# ab_v10.net
KiCad netlist of a schematic drawn in EAGLE
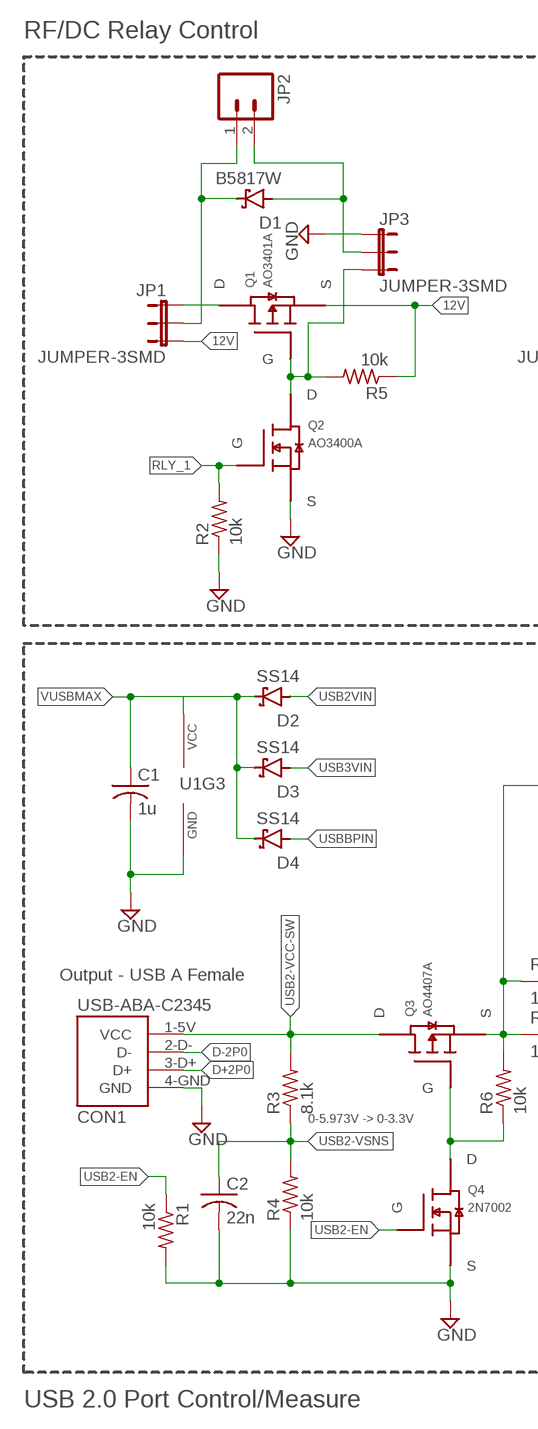
[diagram p0: schematic, sheet 1, part 1 of 2]
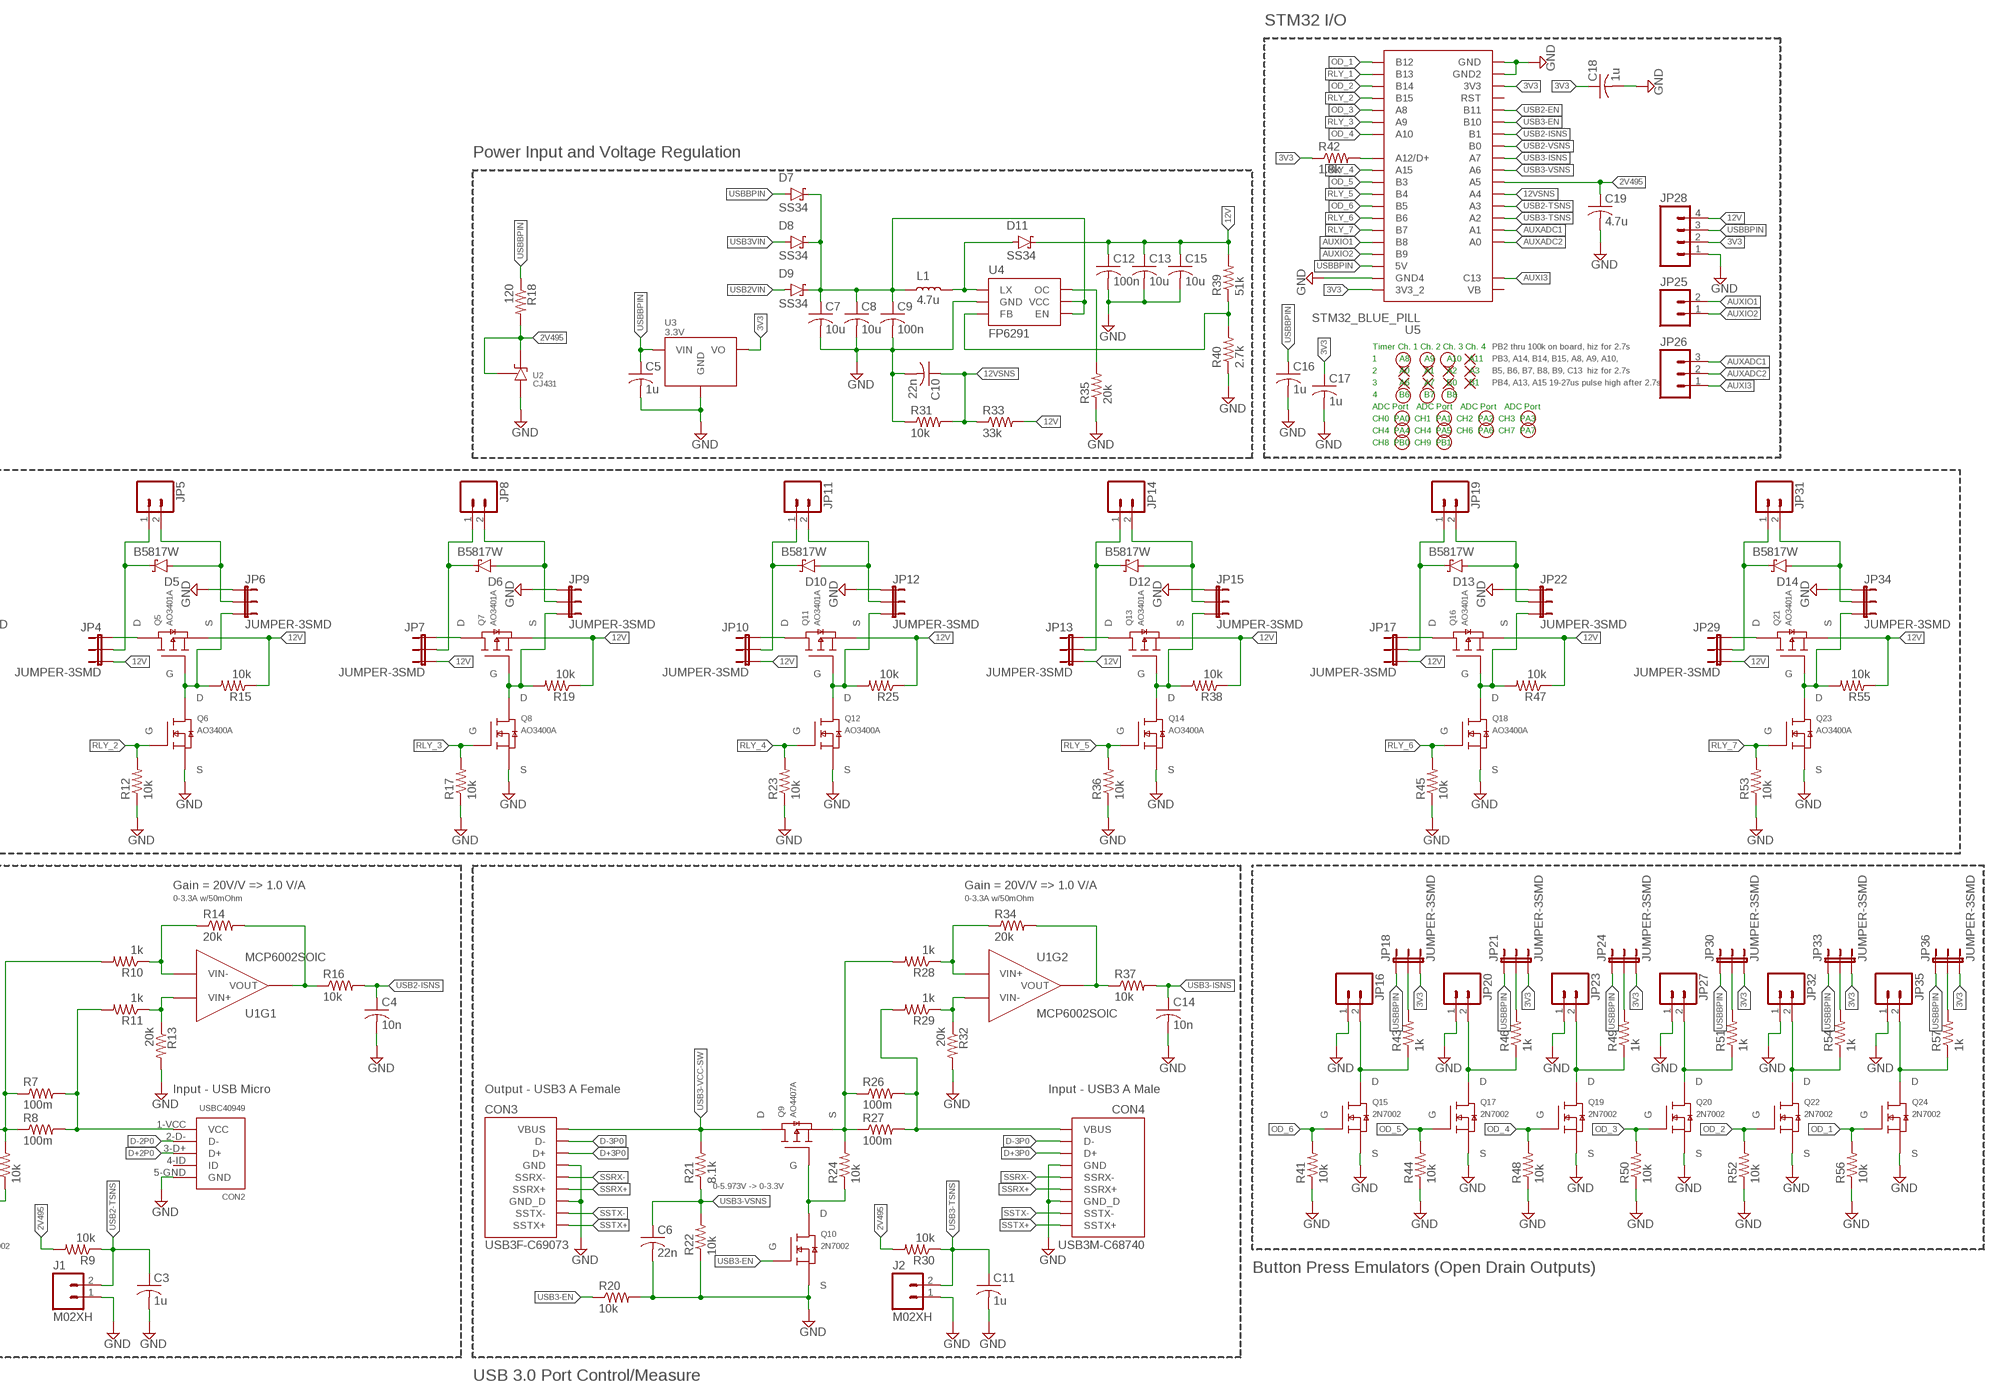
[diagram p1: schematic, sheet 1, part 2 of 2]

(export (version "E")
  (design (tool "Eeschema 10.0.6"))
  (components
    (comp (ref "C1")
      (value "1u")
      (footprint "eagle-import:C0402")
      (libsource (lib "eagle-import") (part "C-USC0402"))
    )
    (comp (ref "C2")
      (value "22n")
      (footprint "eagle-import:C0402")
      (libsource (lib "eagle-import") (part "C-USC0402"))
    )
    (comp (ref "C3")
      (value "1u")
      (footprint "eagle-import:C0402")
      (libsource (lib "eagle-import") (part "C-USC0402"))
    )
    (comp (ref "C4")
      (value "10n")
      (footprint "eagle-import:C0402")
      (libsource (lib "eagle-import") (part "C-USC0402"))
    )
    (comp (ref "C5")
      (value "1u")
      (footprint "eagle-import:C0402")
      (libsource (lib "eagle-import") (part "C-USC0402"))
    )
    (comp (ref "C6")
      (value "22n")
      (footprint "eagle-import:C0402")
      (libsource (lib "eagle-import") (part "C-USC0402"))
    )
    (comp (ref "C7")
      (value "10u")
      (footprint "eagle-import:C0603")
      (libsource (lib "eagle-import") (part "C-USC0603"))
    )
    (comp (ref "C8")
      (value "10u")
      (footprint "eagle-import:C0603")
      (libsource (lib "eagle-import") (part "C-USC0603"))
    )
    (comp (ref "C9")
      (value "100n")
      (footprint "eagle-import:C0402")
      (libsource (lib "eagle-import") (part "C-USC0402"))
    )
    (comp (ref "C10")
      (value "22n")
      (footprint "eagle-import:C0402")
      (libsource (lib "eagle-import") (part "C-USC0402"))
    )
    (comp (ref "C11")
      (value "1u")
      (footprint "eagle-import:C0402")
      (libsource (lib "eagle-import") (part "C-USC0402"))
    )
    (comp (ref "C12")
      (value "100n")
      (footprint "eagle-import:C0402")
      (libsource (lib "eagle-import") (part "C-USC0402"))
    )
    (comp (ref "C13")
      (value "10u")
      (footprint "eagle-import:C0805")
      (libsource (lib "eagle-import") (part "C-USC0805"))
    )
    (comp (ref "C14")
      (value "10n")
      (footprint "eagle-import:C0402")
      (libsource (lib "eagle-import") (part "C-USC0402"))
    )
    (comp (ref "C15")
      (value "10u")
      (footprint "eagle-import:C0805")
      (libsource (lib "eagle-import") (part "C-USC0805"))
    )
    (comp (ref "C16")
      (value "1u")
      (footprint "eagle-import:C0402")
      (libsource (lib "eagle-import") (part "C-USC0402"))
    )
    (comp (ref "C17")
      (value "1u")
      (footprint "eagle-import:C0402")
      (libsource (lib "eagle-import") (part "C-USC0402"))
    )
    (comp (ref "C18")
      (value "1u")
      (footprint "eagle-import:C0402")
      (libsource (lib "eagle-import") (part "C-USC0402"))
    )
    (comp (ref "C19")
      (value "4.7u")
      (footprint "eagle-import:C0402")
      (libsource (lib "eagle-import") (part "C-USC0402"))
    )
    (comp (ref "CON1")
      (value "USB-ABA-C2345")
      (footprint "eagle-import:USB_A_C2345")
      (libsource (lib "eagle-import") (part "USB-ABA-C2345"))
    )
    (comp (ref "CON2")
      (value "USBC40949")
      (footprint "eagle-import:MICRO_USB-B_C40949")
      (libsource (lib "eagle-import") (part "USBC40949"))
    )
    (comp (ref "CON3")
      (value "USB3F-C69073")
      (footprint "eagle-import:USB3-F-C69073")
      (libsource (lib "eagle-import") (part "USB3F-C69073"))
    )
    (comp (ref "CON4")
      (value "USB3M-C68740")
      (footprint "eagle-import:USB3-M-C68740")
      (libsource (lib "eagle-import") (part "USB3M-C68740"))
    )
    (comp (ref "D1")
      (value "B5817W")
      (footprint "eagle-import:SOD123W")
      (libsource (lib "eagle-import") (part "PMEG3020ER"))
    )
    (comp (ref "D2")
      (value "SS14")
      (footprint "eagle-import:SMA")
      (libsource (lib "eagle-import") (part "DIODE_SCHOTTKY_SMSSMA"))
    )
    (comp (ref "D3")
      (value "SS14")
      (footprint "eagle-import:SMA")
      (libsource (lib "eagle-import") (part "DIODE_SCHOTTKY_SMSSMA"))
    )
    (comp (ref "D4")
      (value "SS14")
      (footprint "eagle-import:SMA")
      (libsource (lib "eagle-import") (part "DIODE_SCHOTTKY_SMSSMA"))
    )
    (comp (ref "D5")
      (value "B5817W")
      (footprint "eagle-import:SOD123W")
      (libsource (lib "eagle-import") (part "PMEG3020ER"))
    )
    (comp (ref "D6")
      (value "B5817W")
      (footprint "eagle-import:SOD123W")
      (libsource (lib "eagle-import") (part "PMEG3020ER"))
    )
    (comp (ref "D7")
      (value "SS34")
      (footprint "eagle-import:SMA")
      (libsource (lib "eagle-import") (part "DIODE_SCHOTTKY_SMSSMA"))
    )
    (comp (ref "D8")
      (value "SS34")
      (footprint "eagle-import:SMA")
      (libsource (lib "eagle-import") (part "DIODE_SCHOTTKY_SMSSMA"))
    )
    (comp (ref "D9")
      (value "SS34")
      (footprint "eagle-import:SMA")
      (libsource (lib "eagle-import") (part "DIODE_SCHOTTKY_SMSSMA"))
    )
    (comp (ref "D10")
      (value "B5817W")
      (footprint "eagle-import:SOD123W")
      (libsource (lib "eagle-import") (part "PMEG3020ER"))
    )
    (comp (ref "D11")
      (value "SS34")
      (footprint "eagle-import:SMA")
      (libsource (lib "eagle-import") (part "DIODE_SCHOTTKY_SMSSMA"))
    )
    (comp (ref "D12")
      (value "B5817W")
      (footprint "eagle-import:SOD123W")
      (libsource (lib "eagle-import") (part "PMEG3020ER"))
    )
    (comp (ref "D13")
      (value "B5817W")
      (footprint "eagle-import:SOD123W")
      (libsource (lib "eagle-import") (part "PMEG3020ER"))
    )
    (comp (ref "D14")
      (value "B5817W")
      (footprint "eagle-import:SOD123W")
      (libsource (lib "eagle-import") (part "PMEG3020ER"))
    )
    (comp (ref "J1")
      (value "M02XH")
      (footprint "eagle-import:B2B-XH-A")
      (libsource (lib "eagle-import") (part "M02XH"))
    )
    (comp (ref "J2")
      (value "M02XH")
      (footprint "eagle-import:B2B-XH-A")
      (libsource (lib "eagle-import") (part "M02XH"))
    )
    (comp (ref "JP1")
      (value "JUMPER-3SMD")
      (footprint "eagle-import:SJ_3")
      (libsource (lib "eagle-import") (part "JUMPER-3SMD"))
    )
    (comp (ref "JP2")
      (value "M02PTH")
      (footprint "eagle-import:1X02")
      (libsource (lib "eagle-import") (part "M02PTH"))
    )
    (comp (ref "JP3")
      (value "JUMPER-3SMD")
      (footprint "eagle-import:SJ_3")
      (libsource (lib "eagle-import") (part "JUMPER-3SMD"))
    )
    (comp (ref "JP4")
      (value "JUMPER-3SMD")
      (footprint "eagle-import:SJ_3")
      (libsource (lib "eagle-import") (part "JUMPER-3SMD"))
    )
    (comp (ref "JP5")
      (value "M02PTH")
      (footprint "eagle-import:1X02")
      (libsource (lib "eagle-import") (part "M02PTH"))
    )
    (comp (ref "JP6")
      (value "JUMPER-3SMD")
      (footprint "eagle-import:SJ_3")
      (libsource (lib "eagle-import") (part "JUMPER-3SMD"))
    )
    (comp (ref "JP7")
      (value "JUMPER-3SMD")
      (footprint "eagle-import:SJ_3")
      (libsource (lib "eagle-import") (part "JUMPER-3SMD"))
    )
    (comp (ref "JP8")
      (value "M02PTH")
      (footprint "eagle-import:1X02")
      (libsource (lib "eagle-import") (part "M02PTH"))
    )
    (comp (ref "JP9")
      (value "JUMPER-3SMD")
      (footprint "eagle-import:SJ_3")
      (libsource (lib "eagle-import") (part "JUMPER-3SMD"))
    )
    (comp (ref "JP10")
      (value "JUMPER-3SMD")
      (footprint "eagle-import:SJ_3")
      (libsource (lib "eagle-import") (part "JUMPER-3SMD"))
    )
    (comp (ref "JP11")
      (value "M02PTH")
      (footprint "eagle-import:1X02")
      (libsource (lib "eagle-import") (part "M02PTH"))
    )
    (comp (ref "JP12")
      (value "JUMPER-3SMD")
      (footprint "eagle-import:SJ_3")
      (libsource (lib "eagle-import") (part "JUMPER-3SMD"))
    )
    (comp (ref "JP13")
      (value "JUMPER-3SMD")
      (footprint "eagle-import:SJ_3")
      (libsource (lib "eagle-import") (part "JUMPER-3SMD"))
    )
    (comp (ref "JP14")
      (value "M02PTH")
      (footprint "eagle-import:1X02")
      (libsource (lib "eagle-import") (part "M02PTH"))
    )
    (comp (ref "JP15")
      (value "JUMPER-3SMD")
      (footprint "eagle-import:SJ_3")
      (libsource (lib "eagle-import") (part "JUMPER-3SMD"))
    )
    (comp (ref "JP16")
      (value "M02PTH")
      (footprint "eagle-import:1X02")
      (libsource (lib "eagle-import") (part "M02PTH"))
    )
    (comp (ref "JP17")
      (value "JUMPER-3SMD")
      (footprint "eagle-import:SJ_3")
      (libsource (lib "eagle-import") (part "JUMPER-3SMD"))
    )
    (comp (ref "JP18")
      (value "JUMPER-3SMD")
      (footprint "eagle-import:SJ_3")
      (libsource (lib "eagle-import") (part "JUMPER-3SMD"))
    )
    (comp (ref "JP19")
      (value "M02PTH")
      (footprint "eagle-import:1X02")
      (libsource (lib "eagle-import") (part "M02PTH"))
    )
    (comp (ref "JP20")
      (value "M02PTH")
      (footprint "eagle-import:1X02")
      (libsource (lib "eagle-import") (part "M02PTH"))
    )
    (comp (ref "JP21")
      (value "JUMPER-3SMD")
      (footprint "eagle-import:SJ_3")
      (libsource (lib "eagle-import") (part "JUMPER-3SMD"))
    )
    (comp (ref "JP22")
      (value "JUMPER-3SMD")
      (footprint "eagle-import:SJ_3")
      (libsource (lib "eagle-import") (part "JUMPER-3SMD"))
    )
    (comp (ref "JP23")
      (value "M02PTH")
      (footprint "eagle-import:1X02")
      (libsource (lib "eagle-import") (part "M02PTH"))
    )
    (comp (ref "JP24")
      (value "JUMPER-3SMD")
      (footprint "eagle-import:SJ_3")
      (libsource (lib "eagle-import") (part "JUMPER-3SMD"))
    )
    (comp (ref "JP25")
      (value "M02PTH")
      (footprint "eagle-import:1X02")
      (libsource (lib "eagle-import") (part "M02PTH"))
    )
    (comp (ref "JP26")
      (value "M03PTH")
      (footprint "eagle-import:1X03")
      (libsource (lib "eagle-import") (part "M03PTH"))
    )
    (comp (ref "JP27")
      (value "M02PTH")
      (footprint "eagle-import:1X02")
      (libsource (lib "eagle-import") (part "M02PTH"))
    )
    (comp (ref "JP28")
      (value "M04PTH")
      (footprint "eagle-import:1X04")
      (libsource (lib "eagle-import") (part "M04PTH"))
    )
    (comp (ref "JP29")
      (value "JUMPER-3SMD")
      (footprint "eagle-import:SJ_3")
      (libsource (lib "eagle-import") (part "JUMPER-3SMD"))
    )
    (comp (ref "JP30")
      (value "JUMPER-3SMD")
      (footprint "eagle-import:SJ_3")
      (libsource (lib "eagle-import") (part "JUMPER-3SMD"))
    )
    (comp (ref "JP31")
      (value "M02PTH")
      (footprint "eagle-import:1X02")
      (libsource (lib "eagle-import") (part "M02PTH"))
    )
    (comp (ref "JP32")
      (value "M02PTH")
      (footprint "eagle-import:1X02")
      (libsource (lib "eagle-import") (part "M02PTH"))
    )
    (comp (ref "JP33")
      (value "JUMPER-3SMD")
      (footprint "eagle-import:SJ_3")
      (libsource (lib "eagle-import") (part "JUMPER-3SMD"))
    )
    (comp (ref "JP34")
      (value "JUMPER-3SMD")
      (footprint "eagle-import:SJ_3")
      (libsource (lib "eagle-import") (part "JUMPER-3SMD"))
    )
    (comp (ref "JP35")
      (value "M02PTH")
      (footprint "eagle-import:1X02")
      (libsource (lib "eagle-import") (part "M02PTH"))
    )
    (comp (ref "JP36")
      (value "JUMPER-3SMD")
      (footprint "eagle-import:SJ_3")
      (libsource (lib "eagle-import") (part "JUMPER-3SMD"))
    )
    (comp (ref "L1")
      (value "4.7u")
      (footprint "eagle-import:INDUCTOR_6X6")
      (libsource (lib "eagle-import") (part "INDUCTOR6X6"))
    )
    (comp (ref "Q1")
      (value "AO3401A")
      (footprint "eagle-import:SOT23")
      (libsource (lib "eagle-import") (part "AO3401A"))
    )
    (comp (ref "Q2")
      (value "AO3400A")
      (footprint "eagle-import:SOT23")
      (libsource (lib "eagle-import") (part "2N7002P"))
    )
    (comp (ref "Q3")
      (value "AO4407A")
      (footprint "eagle-import:8-SOIC")
      (libsource (lib "eagle-import") (part "P-MOSFET-SOIC8"))
    )
    (comp (ref "Q4")
      (value "2N7002")
      (footprint "eagle-import:SOT23")
      (libsource (lib "eagle-import") (part "2N7002P"))
    )
    (comp (ref "Q5")
      (value "AO3401A")
      (footprint "eagle-import:SOT23")
      (libsource (lib "eagle-import") (part "AO3401A"))
    )
    (comp (ref "Q6")
      (value "AO3400A")
      (footprint "eagle-import:SOT23")
      (libsource (lib "eagle-import") (part "2N7002P"))
    )
    (comp (ref "Q7")
      (value "AO3401A")
      (footprint "eagle-import:SOT23")
      (libsource (lib "eagle-import") (part "AO3401A"))
    )
    (comp (ref "Q8")
      (value "AO3400A")
      (footprint "eagle-import:SOT23")
      (libsource (lib "eagle-import") (part "2N7002P"))
    )
    (comp (ref "Q9")
      (value "AO4407A")
      (footprint "eagle-import:8-SOIC")
      (libsource (lib "eagle-import") (part "P-MOSFET-SOIC8"))
    )
    (comp (ref "Q10")
      (value "2N7002")
      (footprint "eagle-import:SOT23")
      (libsource (lib "eagle-import") (part "2N7002P"))
    )
    (comp (ref "Q11")
      (value "AO3401A")
      (footprint "eagle-import:SOT23")
      (libsource (lib "eagle-import") (part "AO3401A"))
    )
    (comp (ref "Q12")
      (value "AO3400A")
      (footprint "eagle-import:SOT23")
      (libsource (lib "eagle-import") (part "2N7002P"))
    )
    (comp (ref "Q13")
      (value "AO3401A")
      (footprint "eagle-import:SOT23")
      (libsource (lib "eagle-import") (part "AO3401A"))
    )
    (comp (ref "Q14")
      (value "AO3400A")
      (footprint "eagle-import:SOT23")
      (libsource (lib "eagle-import") (part "2N7002P"))
    )
    (comp (ref "Q15")
      (value "2N7002")
      (footprint "eagle-import:SOT23")
      (libsource (lib "eagle-import") (part "2N7002P"))
    )
    (comp (ref "Q16")
      (value "AO3401A")
      (footprint "eagle-import:SOT23")
      (libsource (lib "eagle-import") (part "AO3401A"))
    )
    (comp (ref "Q17")
      (value "2N7002")
      (footprint "eagle-import:SOT23")
      (libsource (lib "eagle-import") (part "2N7002P"))
    )
    (comp (ref "Q18")
      (value "AO3400A")
      (footprint "eagle-import:SOT23")
      (libsource (lib "eagle-import") (part "2N7002P"))
    )
    (comp (ref "Q19")
      (value "2N7002")
      (footprint "eagle-import:SOT23")
      (libsource (lib "eagle-import") (part "2N7002P"))
    )
    (comp (ref "Q20")
      (value "2N7002")
      (footprint "eagle-import:SOT23")
      (libsource (lib "eagle-import") (part "2N7002P"))
    )
    (comp (ref "Q21")
      (value "AO3401A")
      (footprint "eagle-import:SOT23")
      (libsource (lib "eagle-import") (part "AO3401A"))
    )
    (comp (ref "Q22")
      (value "2N7002")
      (footprint "eagle-import:SOT23")
      (libsource (lib "eagle-import") (part "2N7002P"))
    )
    (comp (ref "Q23")
      (value "AO3400A")
      (footprint "eagle-import:SOT23")
      (libsource (lib "eagle-import") (part "2N7002P"))
    )
    (comp (ref "Q24")
      (value "2N7002")
      (footprint "eagle-import:SOT23")
      (libsource (lib "eagle-import") (part "2N7002P"))
    )
    (comp (ref "R1")
      (value "10k")
      (footprint "eagle-import:R0402")
      (libsource (lib "eagle-import") (part "R-US_R0402"))
    )
    (comp (ref "R2")
      (value "10k")
      (footprint "eagle-import:R0402")
      (libsource (lib "eagle-import") (part "R-US_R0402"))
    )
    (comp (ref "R3")
      (value "8.1k")
      (footprint "eagle-import:R0402")
      (libsource (lib "eagle-import") (part "R-US_R0402"))
    )
    (comp (ref "R4")
      (value "10k")
      (footprint "eagle-import:R0402")
      (libsource (lib "eagle-import") (part "R-US_R0402"))
    )
    (comp (ref "R5")
      (value "10k")
      (footprint "eagle-import:R0402")
      (libsource (lib "eagle-import") (part "R-US_R0402"))
    )
    (comp (ref "R6")
      (value "10k")
      (footprint "eagle-import:R0402")
      (libsource (lib "eagle-import") (part "R-US_R0402"))
    )
    (comp (ref "R7")
      (value "100m")
      (footprint "eagle-import:R1206")
      (libsource (lib "eagle-import") (part "R-US_R1206"))
    )
    (comp (ref "R8")
      (value "100m")
      (footprint "eagle-import:R1206")
      (libsource (lib "eagle-import") (part "R-US_R1206"))
    )
    (comp (ref "R9")
      (value "10k")
      (footprint "eagle-import:R0402")
      (libsource (lib "eagle-import") (part "R-US_R0402"))
    )
    (comp (ref "R10")
      (value "1k")
      (footprint "eagle-import:R0402")
      (libsource (lib "eagle-import") (part "R-US_R0402"))
    )
    (comp (ref "R11")
      (value "1k")
      (footprint "eagle-import:R0402")
      (libsource (lib "eagle-import") (part "R-US_R0402"))
    )
    (comp (ref "R12")
      (value "10k")
      (footprint "eagle-import:R0402")
      (libsource (lib "eagle-import") (part "R-US_R0402"))
    )
    (comp (ref "R13")
      (value "20k")
      (footprint "eagle-import:R0402")
      (libsource (lib "eagle-import") (part "R-US_R0402"))
    )
    (comp (ref "R14")
      (value "20k")
      (footprint "eagle-import:R0402")
      (libsource (lib "eagle-import") (part "R-US_R0402"))
    )
    (comp (ref "R15")
      (value "10k")
      (footprint "eagle-import:R0402")
      (libsource (lib "eagle-import") (part "R-US_R0402"))
    )
    (comp (ref "R16")
      (value "10k")
      (footprint "eagle-import:R0402")
      (libsource (lib "eagle-import") (part "R-US_R0402"))
    )
    (comp (ref "R17")
      (value "10k")
      (footprint "eagle-import:R0402")
      (libsource (lib "eagle-import") (part "R-US_R0402"))
    )
    (comp (ref "R18")
      (value "120")
      (footprint "eagle-import:R0402")
      (libsource (lib "eagle-import") (part "R-US_R0402"))
    )
    (comp (ref "R19")
      (value "10k")
      (footprint "eagle-import:R0402")
      (libsource (lib "eagle-import") (part "R-US_R0402"))
    )
    (comp (ref "R20")
      (value "10k")
      (footprint "eagle-import:R0402")
      (libsource (lib "eagle-import") (part "R-US_R0402"))
    )
    (comp (ref "R21")
      (value "8.1k")
      (footprint "eagle-import:R0402")
      (libsource (lib "eagle-import") (part "R-US_R0402"))
    )
    (comp (ref "R22")
      (value "10k")
      (footprint "eagle-import:R0402")
      (libsource (lib "eagle-import") (part "R-US_R0402"))
    )
    (comp (ref "R23")
      (value "10k")
      (footprint "eagle-import:R0402")
      (libsource (lib "eagle-import") (part "R-US_R0402"))
    )
    (comp (ref "R24")
      (value "10k")
      (footprint "eagle-import:R0402")
      (libsource (lib "eagle-import") (part "R-US_R0402"))
    )
    (comp (ref "R25")
      (value "10k")
      (footprint "eagle-import:R0402")
      (libsource (lib "eagle-import") (part "R-US_R0402"))
    )
    (comp (ref "R26")
      (value "100m")
      (footprint "eagle-import:R1206")
      (libsource (lib "eagle-import") (part "R-US_R1206"))
    )
    (comp (ref "R27")
      (value "100m")
      (footprint "eagle-import:R1206")
      (libsource (lib "eagle-import") (part "R-US_R1206"))
    )
    (comp (ref "R28")
      (value "1k")
      (footprint "eagle-import:R0402")
      (libsource (lib "eagle-import") (part "R-US_R0402"))
    )
    (comp (ref "R29")
      (value "1k")
      (footprint "eagle-import:R0402")
      (libsource (lib "eagle-import") (part "R-US_R0402"))
    )
    (comp (ref "R30")
      (value "10k")
      (footprint "eagle-import:R0402")
      (libsource (lib "eagle-import") (part "R-US_R0402"))
    )
    (comp (ref "R31")
      (value "10k")
      (footprint "eagle-import:R0402")
      (libsource (lib "eagle-import") (part "R-US_R0402"))
    )
    (comp (ref "R32")
      (value "20k")
      (footprint "eagle-import:R0402")
      (libsource (lib "eagle-import") (part "R-US_R0402"))
    )
    (comp (ref "R33")
      (value "33k")
      (footprint "eagle-import:R0402")
      (libsource (lib "eagle-import") (part "R-US_R0402"))
    )
    (comp (ref "R34")
      (value "20k")
      (footprint "eagle-import:R0402")
      (libsource (lib "eagle-import") (part "R-US_R0402"))
    )
    (comp (ref "R35")
      (value "20k")
      (footprint "eagle-import:R0402")
      (libsource (lib "eagle-import") (part "R-US_R0402"))
    )
    (comp (ref "R36")
      (value "10k")
      (footprint "eagle-import:R0402")
      (libsource (lib "eagle-import") (part "R-US_R0402"))
    )
    (comp (ref "R37")
      (value "10k")
      (footprint "eagle-import:R0402")
      (libsource (lib "eagle-import") (part "R-US_R0402"))
    )
    (comp (ref "R38")
      (value "10k")
      (footprint "eagle-import:R0402")
      (libsource (lib "eagle-import") (part "R-US_R0402"))
    )
    (comp (ref "R39")
      (value "51k")
      (footprint "eagle-import:R0402")
      (libsource (lib "eagle-import") (part "R-US_R0402"))
    )
    (comp (ref "R40")
      (value "2.7k")
      (footprint "eagle-import:R0402")
      (libsource (lib "eagle-import") (part "R-US_R0402"))
    )
    (comp (ref "R41")
      (value "10k")
      (footprint "eagle-import:R0402")
      (libsource (lib "eagle-import") (part "R-US_R0402"))
    )
    (comp (ref "R42")
      (value "1.8k")
      (footprint "eagle-import:R0402")
      (libsource (lib "eagle-import") (part "R-US_R0402"))
    )
    (comp (ref "R43")
      (value "1k")
      (footprint "eagle-import:R0402")
      (libsource (lib "eagle-import") (part "R-US_R0402"))
    )
    (comp (ref "R44")
      (value "10k")
      (footprint "eagle-import:R0402")
      (libsource (lib "eagle-import") (part "R-US_R0402"))
    )
    (comp (ref "R45")
      (value "10k")
      (footprint "eagle-import:R0402")
      (libsource (lib "eagle-import") (part "R-US_R0402"))
    )
    (comp (ref "R46")
      (value "1k")
      (footprint "eagle-import:R0402")
      (libsource (lib "eagle-import") (part "R-US_R0402"))
    )
    (comp (ref "R47")
      (value "10k")
      (footprint "eagle-import:R0402")
      (libsource (lib "eagle-import") (part "R-US_R0402"))
    )
    (comp (ref "R48")
      (value "10k")
      (footprint "eagle-import:R0402")
      (libsource (lib "eagle-import") (part "R-US_R0402"))
    )
    (comp (ref "R49")
      (value "1k")
      (footprint "eagle-import:R0402")
      (libsource (lib "eagle-import") (part "R-US_R0402"))
    )
    (comp (ref "R50")
      (value "10k")
      (footprint "eagle-import:R0402")
      (libsource (lib "eagle-import") (part "R-US_R0402"))
    )
    (comp (ref "R51")
      (value "1k")
      (footprint "eagle-import:R0402")
      (libsource (lib "eagle-import") (part "R-US_R0402"))
    )
    (comp (ref "R52")
      (value "10k")
      (footprint "eagle-import:R0402")
      (libsource (lib "eagle-import") (part "R-US_R0402"))
    )
    (comp (ref "R53")
      (value "10k")
      (footprint "eagle-import:R0402")
      (libsource (lib "eagle-import") (part "R-US_R0402"))
    )
    (comp (ref "R54")
      (value "1k")
      (footprint "eagle-import:R0402")
      (libsource (lib "eagle-import") (part "R-US_R0402"))
    )
    (comp (ref "R55")
      (value "10k")
      (footprint "eagle-import:R0402")
      (libsource (lib "eagle-import") (part "R-US_R0402"))
    )
    (comp (ref "R56")
      (value "10k")
      (footprint "eagle-import:R0402")
      (libsource (lib "eagle-import") (part "R-US_R0402"))
    )
    (comp (ref "R57")
      (value "1k")
      (footprint "eagle-import:R0402")
      (libsource (lib "eagle-import") (part "R-US_R0402"))
    )
    (comp (ref "U1")
      (value "MCP6002SOIC")
      (footprint "eagle-import:8-SOIC")
      (libsource (lib "eagle-import") (part "MCP6002SOIC"))
    )
    (comp (ref "U2")
      (value "CJ431")
      (footprint "eagle-import:SOT23")
      (libsource (lib "eagle-import") (part "TL431SOT23"))
    )
    (comp (ref "U3")
      (value "3.3V")
      (footprint "eagle-import:SOT-89")
      (libsource (lib "eagle-import") (part "AP1117UR133-B"))
    )
    (comp (ref "U4")
      (value "FP6291")
      (footprint "eagle-import:SOT23-6")
      (libsource (lib "eagle-import") (part "FP6291"))
    )
    (comp (ref "U5")
      (value "STM32_BLUE_PILL")
      (footprint "eagle-import:STM32_BLUE_PILL_USABLE")
      (libsource (lib "eagle-import") (part "STM32_BLUE_PILL"))
    )
  )
  (nets
    (net (code "1") (name "2V495") (class "Default")
      (node (ref "C19") (pin "1") (pinfunction "1_1") (pintype "passive"))
      (node (ref "R18") (pin "2") (pinfunction "2_2") (pintype "passive"))
      (node (ref "R30") (pin "2") (pinfunction "2_2") (pintype "passive"))
      (node (ref "R9") (pin "2") (pinfunction "2_2") (pintype "passive"))
      (node (ref "U2") (pin "1") (pinfunction "K_1") (pintype "passive"))
      (node (ref "U2") (pin "2") (pinfunction "REF_2") (pintype "passive"))
      (node (ref "U5") (pin "A5") (pinfunction "A5_A5") (pintype "bidirectional"))
    )
    (net (code "2") (name "3V3") (class "Default")
      (node (ref "C17") (pin "1") (pinfunction "1_1") (pintype "passive"))
      (node (ref "C18") (pin "1") (pinfunction "1_1") (pintype "passive"))
      (node (ref "JP18") (pin "3") (pinfunction "3_3") (pintype "passive"))
      (node (ref "JP21") (pin "3") (pinfunction "3_3") (pintype "passive"))
      (node (ref "JP24") (pin "3") (pinfunction "3_3") (pintype "passive"))
      (node (ref "JP28") (pin "2") (pinfunction "2_2") (pintype "passive"))
      (node (ref "JP30") (pin "3") (pinfunction "3_3") (pintype "passive"))
      (node (ref "JP33") (pin "3") (pinfunction "3_3") (pintype "passive"))
      (node (ref "JP36") (pin "3") (pinfunction "3_3") (pintype "passive"))
      (node (ref "R42") (pin "1") (pinfunction "1_1") (pintype "passive"))
      (node (ref "U3") (pin "1") (pinfunction "VO_1") (pintype "bidirectional"))
      (node (ref "U5") (pin "3V3") (pinfunction "3V3_3V3") (pintype "bidirectional"))
      (node (ref "U5") (pin "3V3_2") (pinfunction "3V3_2_3V3_2") (pintype "bidirectional"))
    )
    (net (code "3") (name "12V") (class "Default")
      (node (ref "C12") (pin "1") (pinfunction "1_1") (pintype "passive"))
      (node (ref "C13") (pin "1") (pinfunction "1_1") (pintype "passive"))
      (node (ref "C15") (pin "1") (pinfunction "1_1") (pintype "passive"))
      (node (ref "D11") (pin "K") (pinfunction "CATHODE_K") (pintype "passive"))
      (node (ref "JP1") (pin "3") (pinfunction "3_3") (pintype "passive"))
      (node (ref "JP10") (pin "3") (pinfunction "3_3") (pintype "passive"))
      (node (ref "JP13") (pin "3") (pinfunction "3_3") (pintype "passive"))
      (node (ref "JP17") (pin "3") (pinfunction "3_3") (pintype "passive"))
      (node (ref "JP28") (pin "4") (pinfunction "4_4") (pintype "passive"))
      (node (ref "JP29") (pin "3") (pinfunction "3_3") (pintype "passive"))
      (node (ref "JP4") (pin "3") (pinfunction "3_3") (pintype "passive"))
      (node (ref "JP7") (pin "3") (pinfunction "3_3") (pintype "passive"))
      (node (ref "Q1") (pin "2") (pinfunction "S_2") (pintype "bidirectional"))
      (node (ref "Q11") (pin "2") (pinfunction "S_2") (pintype "bidirectional"))
      (node (ref "Q13") (pin "2") (pinfunction "S_2") (pintype "bidirectional"))
      (node (ref "Q16") (pin "2") (pinfunction "S_2") (pintype "bidirectional"))
      (node (ref "Q21") (pin "2") (pinfunction "S_2") (pintype "bidirectional"))
      (node (ref "Q5") (pin "2") (pinfunction "S_2") (pintype "bidirectional"))
      (node (ref "Q7") (pin "2") (pinfunction "S_2") (pintype "bidirectional"))
      (node (ref "R15") (pin "1") (pinfunction "1_1") (pintype "passive"))
      (node (ref "R19") (pin "1") (pinfunction "1_1") (pintype "passive"))
      (node (ref "R25") (pin "1") (pinfunction "1_1") (pintype "passive"))
      (node (ref "R33") (pin "2") (pinfunction "2_2") (pintype "passive"))
      (node (ref "R38") (pin "1") (pinfunction "1_1") (pintype "passive"))
      (node (ref "R39") (pin "2") (pinfunction "2_2") (pintype "passive"))
      (node (ref "R47") (pin "1") (pinfunction "1_1") (pintype "passive"))
      (node (ref "R5") (pin "1") (pinfunction "1_1") (pintype "passive"))
      (node (ref "R55") (pin "1") (pinfunction "1_1") (pintype "passive"))
    )
    (net (code "4") (name "12VSNS") (class "Default")
      (node (ref "C10") (pin "1") (pinfunction "1_1") (pintype "passive"))
      (node (ref "R31") (pin "2") (pinfunction "2_2") (pintype "passive"))
      (node (ref "R33") (pin "1") (pinfunction "1_1") (pintype "passive"))
      (node (ref "U5") (pin "A4") (pinfunction "A4_A4") (pintype "bidirectional"))
    )
    (net (code "5") (name "AUXADC1") (class "Default")
      (node (ref "JP26") (pin "3") (pinfunction "3_3") (pintype "passive"))
      (node (ref "U5") (pin "A1") (pinfunction "A1_A1") (pintype "bidirectional"))
    )
    (net (code "6") (name "AUXADC2") (class "Default")
      (node (ref "JP26") (pin "2") (pinfunction "2_2") (pintype "passive"))
      (node (ref "U5") (pin "A0") (pinfunction "A0_A0") (pintype "bidirectional"))
    )
    (net (code "7") (name "AUXI3") (class "Default")
      (node (ref "JP26") (pin "1") (pinfunction "1_1") (pintype "passive"))
      (node (ref "U5") (pin "C13") (pinfunction "C13_C13") (pintype "bidirectional"))
    )
    (net (code "8") (name "AUXIO1") (class "Default")
      (node (ref "JP25") (pin "2") (pinfunction "2_2") (pintype "passive"))
      (node (ref "U5") (pin "B8") (pinfunction "B8_B8") (pintype "bidirectional"))
    )
    (net (code "9") (name "AUXIO2") (class "Default")
      (node (ref "JP25") (pin "1") (pinfunction "1_1") (pintype "passive"))
      (node (ref "U5") (pin "B9") (pinfunction "B9_B9") (pintype "bidirectional"))
    )
    (net (code "10") (name "D+2P0") (class "Default")
      (node (ref "CON1") (pin "3-D+") (pinfunction "D+_3-D+") (pintype "bidirectional"))
      (node (ref "CON2") (pin "3-D+") (pinfunction "D+_3-D+") (pintype "bidirectional"))
    )
    (net (code "11") (name "D+3P0") (class "Default")
      (node (ref "CON3") (pin "3-D+") (pinfunction "D+_3-D+") (pintype "bidirectional"))
      (node (ref "CON4") (pin "3-D+") (pinfunction "D+_3-D+") (pintype "bidirectional"))
    )
    (net (code "12") (name "D-2P0") (class "Default")
      (node (ref "CON1") (pin "2-D-") (pinfunction "D-_2-D-") (pintype "bidirectional"))
      (node (ref "CON2") (pin "2-D-") (pinfunction "D-_2-D-") (pintype "bidirectional"))
    )
    (net (code "13") (name "D-3P0") (class "Default")
      (node (ref "CON3") (pin "2-D-") (pinfunction "D-_2-D-") (pintype "bidirectional"))
      (node (ref "CON4") (pin "2-D-") (pinfunction "D-_2-D-") (pintype "bidirectional"))
    )
    (net (code "14") (name "GND") (class "Default")
      (node (ref "C1") (pin "2") (pinfunction "2_2") (pintype "passive"))
      (node (ref "C10") (pin "2") (pinfunction "2_2") (pintype "passive"))
      (node (ref "C11") (pin "2") (pinfunction "2_2") (pintype "passive"))
      (node (ref "C12") (pin "2") (pinfunction "2_2") (pintype "passive"))
      (node (ref "C13") (pin "2") (pinfunction "2_2") (pintype "passive"))
      (node (ref "C14") (pin "2") (pinfunction "2_2") (pintype "passive"))
      (node (ref "C15") (pin "2") (pinfunction "2_2") (pintype "passive"))
      (node (ref "C16") (pin "2") (pinfunction "2_2") (pintype "passive"))
      (node (ref "C17") (pin "2") (pinfunction "2_2") (pintype "passive"))
      (node (ref "C18") (pin "2") (pinfunction "2_2") (pintype "passive"))
      (node (ref "C19") (pin "2") (pinfunction "2_2") (pintype "passive"))
      (node (ref "C2") (pin "2") (pinfunction "2_2") (pintype "passive"))
      (node (ref "C3") (pin "2") (pinfunction "2_2") (pintype "passive"))
      (node (ref "C4") (pin "2") (pinfunction "2_2") (pintype "passive"))
      (node (ref "C5") (pin "2") (pinfunction "2_2") (pintype "passive"))
      (node (ref "C6") (pin "2") (pinfunction "2_2") (pintype "passive"))
      (node (ref "C7") (pin "2") (pinfunction "2_2") (pintype "passive"))
      (node (ref "C8") (pin "2") (pinfunction "2_2") (pintype "passive"))
      (node (ref "C9") (pin "2") (pinfunction "2_2") (pintype "passive"))
      (node (ref "CON1") (pin "4-GND") (pinfunction "GND_4-GND") (pintype "bidirectional"))
      (node (ref "CON2") (pin "5-GND") (pinfunction "GND_5-GND") (pintype "bidirectional"))
      (node (ref "CON3") (pin "4-GND") (pinfunction "GND_4-GND") (pintype "bidirectional"))
      (node (ref "CON3") (pin "7-GND") (pinfunction "GND_D_7-GND") (pintype "bidirectional"))
      (node (ref "CON4") (pin "4-GND") (pinfunction "GND_4-GND") (pintype "bidirectional"))
      (node (ref "CON4") (pin "7-GNDD") (pinfunction "GND_D_7-GNDD") (pintype "bidirectional"))
      (node (ref "J1") (pin "1") (pinfunction "1_1") (pintype "passive"))
      (node (ref "J2") (pin "1") (pinfunction "1_1") (pintype "passive"))
      (node (ref "JP12") (pin "1") (pinfunction "1_1") (pintype "passive"))
      (node (ref "JP15") (pin "1") (pinfunction "1_1") (pintype "passive"))
      (node (ref "JP16") (pin "1") (pinfunction "1_1") (pintype "passive"))
      (node (ref "JP20") (pin "1") (pinfunction "1_1") (pintype "passive"))
      (node (ref "JP22") (pin "1") (pinfunction "1_1") (pintype "passive"))
      (node (ref "JP23") (pin "1") (pinfunction "1_1") (pintype "passive"))
      (node (ref "JP27") (pin "1") (pinfunction "1_1") (pintype "passive"))
      (node (ref "JP28") (pin "1") (pinfunction "1_1") (pintype "passive"))
      (node (ref "JP3") (pin "1") (pinfunction "1_1") (pintype "passive"))
      (node (ref "JP32") (pin "1") (pinfunction "1_1") (pintype "passive"))
      (node (ref "JP34") (pin "1") (pinfunction "1_1") (pintype "passive"))
      (node (ref "JP35") (pin "1") (pinfunction "1_1") (pintype "passive"))
      (node (ref "JP6") (pin "1") (pinfunction "1_1") (pintype "passive"))
      (node (ref "JP9") (pin "1") (pinfunction "1_1") (pintype "passive"))
      (node (ref "Q10") (pin "2") (pinfunction "S_2") (pintype "bidirectional"))
      (node (ref "Q12") (pin "2") (pinfunction "S_2") (pintype "bidirectional"))
      (node (ref "Q14") (pin "2") (pinfunction "S_2") (pintype "bidirectional"))
      (node (ref "Q15") (pin "2") (pinfunction "S_2") (pintype "bidirectional"))
      (node (ref "Q17") (pin "2") (pinfunction "S_2") (pintype "bidirectional"))
      (node (ref "Q18") (pin "2") (pinfunction "S_2") (pintype "bidirectional"))
      (node (ref "Q19") (pin "2") (pinfunction "S_2") (pintype "bidirectional"))
      (node (ref "Q2") (pin "2") (pinfunction "S_2") (pintype "bidirectional"))
      (node (ref "Q20") (pin "2") (pinfunction "S_2") (pintype "bidirectional"))
      (node (ref "Q22") (pin "2") (pinfunction "S_2") (pintype "bidirectional"))
      (node (ref "Q23") (pin "2") (pinfunction "S_2") (pintype "bidirectional"))
      (node (ref "Q24") (pin "2") (pinfunction "S_2") (pintype "bidirectional"))
      (node (ref "Q4") (pin "2") (pinfunction "S_2") (pintype "bidirectional"))
      (node (ref "Q6") (pin "2") (pinfunction "S_2") (pintype "bidirectional"))
      (node (ref "Q8") (pin "2") (pinfunction "S_2") (pintype "bidirectional"))
      (node (ref "R1") (pin "2") (pinfunction "2_2") (pintype "passive"))
      (node (ref "R12") (pin "1") (pinfunction "1_1") (pintype "passive"))
      (node (ref "R13") (pin "2") (pinfunction "2_2") (pintype "passive"))
      (node (ref "R17") (pin "1") (pinfunction "1_1") (pintype "passive"))
      (node (ref "R2") (pin "1") (pinfunction "1_1") (pintype "passive"))
      (node (ref "R20") (pin "2") (pinfunction "2_2") (pintype "passive"))
      (node (ref "R22") (pin "1") (pinfunction "1_1") (pintype "passive"))
      (node (ref "R23") (pin "1") (pinfunction "1_1") (pintype "passive"))
      (node (ref "R31") (pin "1") (pinfunction "1_1") (pintype "passive"))
      (node (ref "R32") (pin "2") (pinfunction "2_2") (pintype "passive"))
      (node (ref "R35") (pin "1") (pinfunction "1_1") (pintype "passive"))
      (node (ref "R36") (pin "1") (pinfunction "1_1") (pintype "passive"))
      (node (ref "R4") (pin "1") (pinfunction "1_1") (pintype "passive"))
      (node (ref "R40") (pin "1") (pinfunction "1_1") (pintype "passive"))
      (node (ref "R41") (pin "1") (pinfunction "1_1") (pintype "passive"))
      (node (ref "R44") (pin "1") (pinfunction "1_1") (pintype "passive"))
      (node (ref "R45") (pin "1") (pinfunction "1_1") (pintype "passive"))
      (node (ref "R48") (pin "1") (pinfunction "1_1") (pintype "passive"))
      (node (ref "R50") (pin "1") (pinfunction "1_1") (pintype "passive"))
      (node (ref "R52") (pin "1") (pinfunction "1_1") (pintype "passive"))
      (node (ref "R53") (pin "1") (pinfunction "1_1") (pintype "passive"))
      (node (ref "R56") (pin "1") (pinfunction "1_1") (pintype "passive"))
      (node (ref "U1") (pin "4") (pinfunction "GND_4") (pintype "power_in"))
      (node (ref "U2") (pin "3") (pinfunction "A_3") (pintype "passive"))
      (node (ref "U3") (pin "2") (pinfunction "GND_2") (pintype "bidirectional"))
      (node (ref "U3") (pin "2@1") (pinfunction "GND_2@1") (pintype "bidirectional"))
      (node (ref "U4") (pin "2") (pinfunction "GND_2") (pintype "bidirectional"))
      (node (ref "U5") (pin "GND") (pinfunction "GND_GND") (pintype "bidirectional"))
      (node (ref "U5") (pin "GND2") (pinfunction "GND2_GND2") (pintype "bidirectional"))
      (node (ref "U5") (pin "GND4") (pinfunction "GND4_GND4") (pintype "bidirectional"))
    )
    (net (code "15") (name "Net-(D1-ANODE)") (class "Default")
      (node (ref "D1") (pin "A") (pinfunction "ANODE_A") (pintype "passive"))
      (node (ref "JP2") (pin "2") (pinfunction "2_2") (pintype "passive"))
      (node (ref "JP3") (pin "2") (pinfunction "2_2") (pintype "passive"))
    )
    (net (code "16") (name "Net-(D1-CATHODE)") (class "Default")
      (node (ref "D1") (pin "K") (pinfunction "CATHODE_K") (pintype "passive"))
      (node (ref "JP1") (pin "2") (pinfunction "2_2") (pintype "passive"))
      (node (ref "JP2") (pin "1") (pinfunction "1_1") (pintype "passive"))
    )
    (net (code "17") (name "Net-(D5-ANODE)") (class "Default")
      (node (ref "D5") (pin "A") (pinfunction "ANODE_A") (pintype "passive"))
      (node (ref "JP5") (pin "2") (pinfunction "2_2") (pintype "passive"))
      (node (ref "JP6") (pin "2") (pinfunction "2_2") (pintype "passive"))
    )
    (net (code "18") (name "Net-(D5-CATHODE)") (class "Default")
      (node (ref "D5") (pin "K") (pinfunction "CATHODE_K") (pintype "passive"))
      (node (ref "JP4") (pin "2") (pinfunction "2_2") (pintype "passive"))
      (node (ref "JP5") (pin "1") (pinfunction "1_1") (pintype "passive"))
    )
    (net (code "19") (name "Net-(D6-ANODE)") (class "Default")
      (node (ref "D6") (pin "A") (pinfunction "ANODE_A") (pintype "passive"))
      (node (ref "JP8") (pin "2") (pinfunction "2_2") (pintype "passive"))
      (node (ref "JP9") (pin "2") (pinfunction "2_2") (pintype "passive"))
    )
    (net (code "20") (name "Net-(D6-CATHODE)") (class "Default")
      (node (ref "D6") (pin "K") (pinfunction "CATHODE_K") (pintype "passive"))
      (node (ref "JP7") (pin "2") (pinfunction "2_2") (pintype "passive"))
      (node (ref "JP8") (pin "1") (pinfunction "1_1") (pintype "passive"))
    )
    (net (code "21") (name "Net-(D7-CATHODE)") (class "Default")
      (node (ref "C7") (pin "1") (pinfunction "1_1") (pintype "passive"))
      (node (ref "C8") (pin "1") (pinfunction "1_1") (pintype "passive"))
      (node (ref "C9") (pin "1") (pinfunction "1_1") (pintype "passive"))
      (node (ref "D7") (pin "K") (pinfunction "CATHODE_K") (pintype "passive"))
      (node (ref "D8") (pin "K") (pinfunction "CATHODE_K") (pintype "passive"))
      (node (ref "D9") (pin "K") (pinfunction "CATHODE_K") (pintype "passive"))
      (node (ref "L1") (pin "1") (pinfunction "P$1_1") (pintype "passive"))
      (node (ref "U4") (pin "4") (pinfunction "EN_4") (pintype "bidirectional"))
      (node (ref "U4") (pin "5") (pinfunction "VCC_5") (pintype "bidirectional"))
    )
    (net (code "22") (name "Net-(D10-ANODE)") (class "Default")
      (node (ref "D10") (pin "A") (pinfunction "ANODE_A") (pintype "passive"))
      (node (ref "JP11") (pin "2") (pinfunction "2_2") (pintype "passive"))
      (node (ref "JP12") (pin "2") (pinfunction "2_2") (pintype "passive"))
    )
    (net (code "23") (name "Net-(D10-CATHODE)") (class "Default")
      (node (ref "D10") (pin "K") (pinfunction "CATHODE_K") (pintype "passive"))
      (node (ref "JP10") (pin "2") (pinfunction "2_2") (pintype "passive"))
      (node (ref "JP11") (pin "1") (pinfunction "1_1") (pintype "passive"))
    )
    (net (code "24") (name "Net-(D11-ANODE)") (class "Default")
      (node (ref "D11") (pin "A") (pinfunction "ANODE_A") (pintype "passive"))
      (node (ref "L1") (pin "2") (pinfunction "P$2_2") (pintype "passive"))
      (node (ref "U4") (pin "1") (pinfunction "LX_1") (pintype "bidirectional"))
    )
    (net (code "25") (name "Net-(D12-ANODE)") (class "Default")
      (node (ref "D12") (pin "A") (pinfunction "ANODE_A") (pintype "passive"))
      (node (ref "JP14") (pin "2") (pinfunction "2_2") (pintype "passive"))
      (node (ref "JP15") (pin "2") (pinfunction "2_2") (pintype "passive"))
    )
    (net (code "26") (name "Net-(D12-CATHODE)") (class "Default")
      (node (ref "D12") (pin "K") (pinfunction "CATHODE_K") (pintype "passive"))
      (node (ref "JP13") (pin "2") (pinfunction "2_2") (pintype "passive"))
      (node (ref "JP14") (pin "1") (pinfunction "1_1") (pintype "passive"))
    )
    (net (code "27") (name "Net-(D13-ANODE)") (class "Default")
      (node (ref "D13") (pin "A") (pinfunction "ANODE_A") (pintype "passive"))
      (node (ref "JP19") (pin "2") (pinfunction "2_2") (pintype "passive"))
      (node (ref "JP22") (pin "2") (pinfunction "2_2") (pintype "passive"))
    )
    (net (code "28") (name "Net-(D13-CATHODE)") (class "Default")
      (node (ref "D13") (pin "K") (pinfunction "CATHODE_K") (pintype "passive"))
      (node (ref "JP17") (pin "2") (pinfunction "2_2") (pintype "passive"))
      (node (ref "JP19") (pin "1") (pinfunction "1_1") (pintype "passive"))
    )
    (net (code "29") (name "Net-(D14-ANODE)") (class "Default")
      (node (ref "D14") (pin "A") (pinfunction "ANODE_A") (pintype "passive"))
      (node (ref "JP31") (pin "2") (pinfunction "2_2") (pintype "passive"))
      (node (ref "JP34") (pin "2") (pinfunction "2_2") (pintype "passive"))
    )
    (net (code "30") (name "Net-(D14-CATHODE)") (class "Default")
      (node (ref "D14") (pin "K") (pinfunction "CATHODE_K") (pintype "passive"))
      (node (ref "JP29") (pin "2") (pinfunction "2_2") (pintype "passive"))
      (node (ref "JP31") (pin "1") (pinfunction "1_1") (pintype "passive"))
    )
    (net (code "31") (name "Net-(JP18-Pad2)") (class "Default")
      (node (ref "JP18") (pin "2") (pinfunction "2_2") (pintype "passive"))
      (node (ref "R43") (pin "2") (pinfunction "2_2") (pintype "passive"))
    )
    (net (code "32") (name "Net-(JP21-Pad2)") (class "Default")
      (node (ref "JP21") (pin "2") (pinfunction "2_2") (pintype "passive"))
      (node (ref "R46") (pin "2") (pinfunction "2_2") (pintype "passive"))
    )
    (net (code "33") (name "Net-(JP24-Pad2)") (class "Default")
      (node (ref "JP24") (pin "2") (pinfunction "2_2") (pintype "passive"))
      (node (ref "R49") (pin "2") (pinfunction "2_2") (pintype "passive"))
    )
    (net (code "34") (name "Net-(JP30-Pad2)") (class "Default")
      (node (ref "JP30") (pin "2") (pinfunction "2_2") (pintype "passive"))
      (node (ref "R51") (pin "2") (pinfunction "2_2") (pintype "passive"))
    )
    (net (code "35") (name "Net-(JP33-Pad2)") (class "Default")
      (node (ref "JP33") (pin "2") (pinfunction "2_2") (pintype "passive"))
      (node (ref "R54") (pin "2") (pinfunction "2_2") (pintype "passive"))
    )
    (net (code "36") (name "Net-(JP36-Pad2)") (class "Default")
      (node (ref "JP36") (pin "2") (pinfunction "2_2") (pintype "passive"))
      (node (ref "R57") (pin "2") (pinfunction "2_2") (pintype "passive"))
    )
    (net (code "37") (name "Net-(Q1-D)") (class "Default")
      (node (ref "JP1") (pin "1") (pinfunction "1_1") (pintype "passive"))
      (node (ref "Q1") (pin "3") (pinfunction "D_3") (pintype "bidirectional"))
    )
    (net (code "38") (name "Net-(Q1-G)") (class "Default")
      (node (ref "JP3") (pin "3") (pinfunction "3_3") (pintype "passive"))
      (node (ref "Q1") (pin "1") (pinfunction "G_1") (pintype "bidirectional"))
      (node (ref "Q2") (pin "3") (pinfunction "D_3") (pintype "bidirectional"))
      (node (ref "R5") (pin "2") (pinfunction "2_2") (pintype "passive"))
    )
    (net (code "39") (name "Net-(Q3-G)") (class "Default")
      (node (ref "Q3") (pin "4") (pinfunction "G_4") (pintype "bidirectional"))
      (node (ref "Q4") (pin "3") (pinfunction "D_3") (pintype "bidirectional"))
      (node (ref "R6") (pin "1") (pinfunction "1_1") (pintype "passive"))
    )
    (net (code "40") (name "Net-(Q3-S-Pad1)") (class "Default")
      (node (ref "Q3") (pin "1") (pinfunction "S_1") (pintype "bidirectional"))
      (node (ref "Q3") (pin "2") (pinfunction "S_2") (pintype "bidirectional"))
      (node (ref "Q3") (pin "3") (pinfunction "S_3") (pintype "bidirectional"))
      (node (ref "R10") (pin "2") (pinfunction "2_2") (pintype "passive"))
      (node (ref "R6") (pin "2") (pinfunction "2_2") (pintype "passive"))
      (node (ref "R7") (pin "1") (pinfunction "1_1") (pintype "passive"))
      (node (ref "R8") (pin "1") (pinfunction "1_1") (pintype "passive"))
    )
    (net (code "41") (name "Net-(Q5-D)") (class "Default")
      (node (ref "JP4") (pin "1") (pinfunction "1_1") (pintype "passive"))
      (node (ref "Q5") (pin "3") (pinfunction "D_3") (pintype "bidirectional"))
    )
    (net (code "42") (name "Net-(Q5-G)") (class "Default")
      (node (ref "JP6") (pin "3") (pinfunction "3_3") (pintype "passive"))
      (node (ref "Q5") (pin "1") (pinfunction "G_1") (pintype "bidirectional"))
      (node (ref "Q6") (pin "3") (pinfunction "D_3") (pintype "bidirectional"))
      (node (ref "R15") (pin "2") (pinfunction "2_2") (pintype "passive"))
    )
    (net (code "43") (name "Net-(Q7-D)") (class "Default")
      (node (ref "JP7") (pin "1") (pinfunction "1_1") (pintype "passive"))
      (node (ref "Q7") (pin "3") (pinfunction "D_3") (pintype "bidirectional"))
    )
    (net (code "44") (name "Net-(Q7-G)") (class "Default")
      (node (ref "JP9") (pin "3") (pinfunction "3_3") (pintype "passive"))
      (node (ref "Q7") (pin "1") (pinfunction "G_1") (pintype "bidirectional"))
      (node (ref "Q8") (pin "3") (pinfunction "D_3") (pintype "bidirectional"))
      (node (ref "R19") (pin "2") (pinfunction "2_2") (pintype "passive"))
    )
    (net (code "45") (name "Net-(Q9-S-Pad1)") (class "Default")
      (node (ref "Q9") (pin "1") (pinfunction "S_1") (pintype "bidirectional"))
      (node (ref "Q9") (pin "2") (pinfunction "S_2") (pintype "bidirectional"))
      (node (ref "Q9") (pin "3") (pinfunction "S_3") (pintype "bidirectional"))
      (node (ref "R24") (pin "2") (pinfunction "2_2") (pintype "passive"))
      (node (ref "R26") (pin "1") (pinfunction "1_1") (pintype "passive"))
      (node (ref "R27") (pin "1") (pinfunction "1_1") (pintype "passive"))
      (node (ref "R28") (pin "2") (pinfunction "2_2") (pintype "passive"))
    )
    (net (code "46") (name "Net-(Q10-D)") (class "Default")
      (node (ref "Q10") (pin "3") (pinfunction "D_3") (pintype "bidirectional"))
      (node (ref "Q9") (pin "4") (pinfunction "G_4") (pintype "bidirectional"))
      (node (ref "R24") (pin "1") (pinfunction "1_1") (pintype "passive"))
    )
    (net (code "47") (name "Net-(Q11-D)") (class "Default")
      (node (ref "JP10") (pin "1") (pinfunction "1_1") (pintype "passive"))
      (node (ref "Q11") (pin "3") (pinfunction "D_3") (pintype "bidirectional"))
    )
    (net (code "48") (name "Net-(Q11-G)") (class "Default")
      (node (ref "JP12") (pin "3") (pinfunction "3_3") (pintype "passive"))
      (node (ref "Q11") (pin "1") (pinfunction "G_1") (pintype "bidirectional"))
      (node (ref "Q12") (pin "3") (pinfunction "D_3") (pintype "bidirectional"))
      (node (ref "R25") (pin "2") (pinfunction "2_2") (pintype "passive"))
    )
    (net (code "49") (name "Net-(Q13-D)") (class "Default")
      (node (ref "JP13") (pin "1") (pinfunction "1_1") (pintype "passive"))
      (node (ref "Q13") (pin "3") (pinfunction "D_3") (pintype "bidirectional"))
    )
    (net (code "50") (name "Net-(Q13-G)") (class "Default")
      (node (ref "JP15") (pin "3") (pinfunction "3_3") (pintype "passive"))
      (node (ref "Q13") (pin "1") (pinfunction "G_1") (pintype "bidirectional"))
      (node (ref "Q14") (pin "3") (pinfunction "D_3") (pintype "bidirectional"))
      (node (ref "R38") (pin "2") (pinfunction "2_2") (pintype "passive"))
    )
    (net (code "51") (name "Net-(Q15-D)") (class "Default")
      (node (ref "JP16") (pin "2") (pinfunction "2_2") (pintype "passive"))
      (node (ref "Q15") (pin "3") (pinfunction "D_3") (pintype "bidirectional"))
      (node (ref "R43") (pin "1") (pinfunction "1_1") (pintype "passive"))
    )
    (net (code "52") (name "Net-(Q16-D)") (class "Default")
      (node (ref "JP17") (pin "1") (pinfunction "1_1") (pintype "passive"))
      (node (ref "Q16") (pin "3") (pinfunction "D_3") (pintype "bidirectional"))
    )
    (net (code "53") (name "Net-(Q16-G)") (class "Default")
      (node (ref "JP22") (pin "3") (pinfunction "3_3") (pintype "passive"))
      (node (ref "Q16") (pin "1") (pinfunction "G_1") (pintype "bidirectional"))
      (node (ref "Q18") (pin "3") (pinfunction "D_3") (pintype "bidirectional"))
      (node (ref "R47") (pin "2") (pinfunction "2_2") (pintype "passive"))
    )
    (net (code "54") (name "Net-(Q17-D)") (class "Default")
      (node (ref "JP20") (pin "2") (pinfunction "2_2") (pintype "passive"))
      (node (ref "Q17") (pin "3") (pinfunction "D_3") (pintype "bidirectional"))
      (node (ref "R46") (pin "1") (pinfunction "1_1") (pintype "passive"))
    )
    (net (code "55") (name "Net-(Q19-D)") (class "Default")
      (node (ref "JP23") (pin "2") (pinfunction "2_2") (pintype "passive"))
      (node (ref "Q19") (pin "3") (pinfunction "D_3") (pintype "bidirectional"))
      (node (ref "R49") (pin "1") (pinfunction "1_1") (pintype "passive"))
    )
    (net (code "56") (name "Net-(Q20-D)") (class "Default")
      (node (ref "JP27") (pin "2") (pinfunction "2_2") (pintype "passive"))
      (node (ref "Q20") (pin "3") (pinfunction "D_3") (pintype "bidirectional"))
      (node (ref "R51") (pin "1") (pinfunction "1_1") (pintype "passive"))
    )
    (net (code "57") (name "Net-(Q21-D)") (class "Default")
      (node (ref "JP29") (pin "1") (pinfunction "1_1") (pintype "passive"))
      (node (ref "Q21") (pin "3") (pinfunction "D_3") (pintype "bidirectional"))
    )
    (net (code "58") (name "Net-(Q21-G)") (class "Default")
      (node (ref "JP34") (pin "3") (pinfunction "3_3") (pintype "passive"))
      (node (ref "Q21") (pin "1") (pinfunction "G_1") (pintype "bidirectional"))
      (node (ref "Q23") (pin "3") (pinfunction "D_3") (pintype "bidirectional"))
      (node (ref "R55") (pin "2") (pinfunction "2_2") (pintype "passive"))
    )
    (net (code "59") (name "Net-(Q22-D)") (class "Default")
      (node (ref "JP32") (pin "2") (pinfunction "2_2") (pintype "passive"))
      (node (ref "Q22") (pin "3") (pinfunction "D_3") (pintype "bidirectional"))
      (node (ref "R54") (pin "1") (pinfunction "1_1") (pintype "passive"))
    )
    (net (code "60") (name "Net-(Q24-D)") (class "Default")
      (node (ref "JP35") (pin "2") (pinfunction "2_2") (pintype "passive"))
      (node (ref "Q24") (pin "3") (pinfunction "D_3") (pintype "bidirectional"))
      (node (ref "R57") (pin "1") (pinfunction "1_1") (pintype "passive"))
    )
    (net (code "61") (name "Net-(U1A-VIN+)") (class "Default")
      (node (ref "R11") (pin "1") (pinfunction "1_1") (pintype "passive"))
      (node (ref "R13") (pin "1") (pinfunction "1_1") (pintype "passive"))
      (node (ref "U1") (pin "3") (pinfunction "VIN+_3") (pintype "bidirectional"))
    )
    (net (code "62") (name "Net-(U1A-VIN-)") (class "Default")
      (node (ref "R10") (pin "1") (pinfunction "1_1") (pintype "passive"))
      (node (ref "R14") (pin "1") (pinfunction "1_1") (pintype "passive"))
      (node (ref "U1") (pin "2") (pinfunction "VIN-_2") (pintype "bidirectional"))
    )
    (net (code "63") (name "Net-(U1A-VOUT)") (class "Default")
      (node (ref "R14") (pin "2") (pinfunction "2_2") (pintype "passive"))
      (node (ref "R16") (pin "1") (pinfunction "1_1") (pintype "passive"))
      (node (ref "U1") (pin "1") (pinfunction "VOUT_1") (pintype "bidirectional"))
    )
    (net (code "64") (name "Net-(U1B-VIN+)") (class "Default")
      (node (ref "R28") (pin "1") (pinfunction "1_1") (pintype "passive"))
      (node (ref "R34") (pin "1") (pinfunction "1_1") (pintype "passive"))
      (node (ref "U1") (pin "5") (pinfunction "VIN+_5") (pintype "bidirectional"))
    )
    (net (code "65") (name "Net-(U1B-VIN-)") (class "Default")
      (node (ref "R29") (pin "1") (pinfunction "1_1") (pintype "passive"))
      (node (ref "R32") (pin "1") (pinfunction "1_1") (pintype "passive"))
      (node (ref "U1") (pin "6") (pinfunction "VIN-_6") (pintype "bidirectional"))
    )
    (net (code "66") (name "Net-(U1B-VOUT)") (class "Default")
      (node (ref "R34") (pin "2") (pinfunction "2_2") (pintype "passive"))
      (node (ref "R37") (pin "1") (pinfunction "1_1") (pintype "passive"))
      (node (ref "U1") (pin "7") (pinfunction "VOUT_7") (pintype "bidirectional"))
    )
    (net (code "67") (name "Net-(U4-FB)") (class "Default")
      (node (ref "R39") (pin "1") (pinfunction "1_1") (pintype "passive"))
      (node (ref "R40") (pin "2") (pinfunction "2_2") (pintype "passive"))
      (node (ref "U4") (pin "3") (pinfunction "FB_3") (pintype "bidirectional"))
    )
    (net (code "68") (name "Net-(U4-OC)") (class "Default")
      (node (ref "R35") (pin "2") (pinfunction "2_2") (pintype "passive"))
      (node (ref "U4") (pin "6") (pinfunction "OC_6") (pintype "bidirectional"))
    )
    (net (code "69") (name "Net-(U5-A12{slash}D+)") (class "Default")
      (node (ref "R42") (pin "2") (pinfunction "2_2") (pintype "passive"))
      (node (ref "U5") (pin "A12") (pinfunction "A12/D+_A12") (pintype "bidirectional"))
    )
    (net (code "70") (name "OD_1") (class "Default")
      (node (ref "Q24") (pin "1") (pinfunction "G_1") (pintype "bidirectional"))
      (node (ref "R56") (pin "2") (pinfunction "2_2") (pintype "passive"))
      (node (ref "U5") (pin "B12") (pinfunction "B12_B12") (pintype "bidirectional"))
    )
    (net (code "71") (name "OD_2") (class "Default")
      (node (ref "Q22") (pin "1") (pinfunction "G_1") (pintype "bidirectional"))
      (node (ref "R52") (pin "2") (pinfunction "2_2") (pintype "passive"))
      (node (ref "U5") (pin "B14") (pinfunction "B14_B14") (pintype "bidirectional"))
    )
    (net (code "72") (name "OD_3") (class "Default")
      (node (ref "Q20") (pin "1") (pinfunction "G_1") (pintype "bidirectional"))
      (node (ref "R50") (pin "2") (pinfunction "2_2") (pintype "passive"))
      (node (ref "U5") (pin "A8") (pinfunction "A8_A8") (pintype "bidirectional"))
    )
    (net (code "73") (name "OD_4") (class "Default")
      (node (ref "Q19") (pin "1") (pinfunction "G_1") (pintype "bidirectional"))
      (node (ref "R48") (pin "2") (pinfunction "2_2") (pintype "passive"))
      (node (ref "U5") (pin "A10") (pinfunction "A10_A10") (pintype "bidirectional"))
    )
    (net (code "74") (name "OD_5") (class "Default")
      (node (ref "Q17") (pin "1") (pinfunction "G_1") (pintype "bidirectional"))
      (node (ref "R44") (pin "2") (pinfunction "2_2") (pintype "passive"))
      (node (ref "U5") (pin "B3") (pinfunction "B3_B3") (pintype "bidirectional"))
    )
    (net (code "75") (name "OD_6") (class "Default")
      (node (ref "Q15") (pin "1") (pinfunction "G_1") (pintype "bidirectional"))
      (node (ref "R41") (pin "2") (pinfunction "2_2") (pintype "passive"))
      (node (ref "U5") (pin "B5") (pinfunction "B5_B5") (pintype "bidirectional"))
    )
    (net (code "76") (name "RLY_1") (class "Default")
      (node (ref "Q2") (pin "1") (pinfunction "G_1") (pintype "bidirectional"))
      (node (ref "R2") (pin "2") (pinfunction "2_2") (pintype "passive"))
      (node (ref "U5") (pin "B13") (pinfunction "B13_B13") (pintype "bidirectional"))
    )
    (net (code "77") (name "RLY_2") (class "Default")
      (node (ref "Q6") (pin "1") (pinfunction "G_1") (pintype "bidirectional"))
      (node (ref "R12") (pin "2") (pinfunction "2_2") (pintype "passive"))
      (node (ref "U5") (pin "B15") (pinfunction "B15_B15") (pintype "bidirectional"))
    )
    (net (code "78") (name "RLY_3") (class "Default")
      (node (ref "Q8") (pin "1") (pinfunction "G_1") (pintype "bidirectional"))
      (node (ref "R17") (pin "2") (pinfunction "2_2") (pintype "passive"))
      (node (ref "U5") (pin "A9") (pinfunction "A9_A9") (pintype "bidirectional"))
    )
    (net (code "79") (name "RLY_4") (class "Default")
      (node (ref "Q12") (pin "1") (pinfunction "G_1") (pintype "bidirectional"))
      (node (ref "R23") (pin "2") (pinfunction "2_2") (pintype "passive"))
      (node (ref "U5") (pin "A15") (pinfunction "A15_A15") (pintype "bidirectional"))
    )
    (net (code "80") (name "RLY_5") (class "Default")
      (node (ref "Q14") (pin "1") (pinfunction "G_1") (pintype "bidirectional"))
      (node (ref "R36") (pin "2") (pinfunction "2_2") (pintype "passive"))
      (node (ref "U5") (pin "B4") (pinfunction "B4_B4") (pintype "bidirectional"))
    )
    (net (code "81") (name "RLY_6") (class "Default")
      (node (ref "Q18") (pin "1") (pinfunction "G_1") (pintype "bidirectional"))
      (node (ref "R45") (pin "2") (pinfunction "2_2") (pintype "passive"))
      (node (ref "U5") (pin "B6") (pinfunction "B6_B6") (pintype "bidirectional"))
    )
    (net (code "82") (name "RLY_7") (class "Default")
      (node (ref "Q23") (pin "1") (pinfunction "G_1") (pintype "bidirectional"))
      (node (ref "R53") (pin "2") (pinfunction "2_2") (pintype "passive"))
      (node (ref "U5") (pin "B7") (pinfunction "B7_B7") (pintype "bidirectional"))
    )
    (net (code "83") (name "SSRX+") (class "Default")
      (node (ref "CON3") (pin "6-SSRX+") (pinfunction "SSRX+_6-SSRX+") (pintype "bidirectional"))
      (node (ref "CON4") (pin "6-SSRX+") (pinfunction "SSRX+_6-SSRX+") (pintype "bidirectional"))
    )
    (net (code "84") (name "SSRX-") (class "Default")
      (node (ref "CON3") (pin "5-SSRX-") (pinfunction "SSRX-_5-SSRX-") (pintype "bidirectional"))
      (node (ref "CON4") (pin "5-SSRX-") (pinfunction "SSRX-_5-SSRX-") (pintype "bidirectional"))
    )
    (net (code "85") (name "SSTX+") (class "Default")
      (node (ref "CON3") (pin "9-SSTX+") (pinfunction "SSTX+_9-SSTX+") (pintype "bidirectional"))
      (node (ref "CON4") (pin "9-SSTX+") (pinfunction "SSTX+_9-SSTX+") (pintype "bidirectional"))
    )
    (net (code "86") (name "SSTX-") (class "Default")
      (node (ref "CON3") (pin "8-SSTX-") (pinfunction "SSTX-_8-SSTX-") (pintype "bidirectional"))
      (node (ref "CON4") (pin "8-SSTX-") (pinfunction "SSTX-_8-SSTX-") (pintype "bidirectional"))
    )
    (net (code "87") (name "USB2-EN") (class "Default")
      (node (ref "Q4") (pin "1") (pinfunction "G_1") (pintype "bidirectional"))
      (node (ref "R1") (pin "1") (pinfunction "1_1") (pintype "passive"))
      (node (ref "U5") (pin "B11") (pinfunction "B11_B11") (pintype "bidirectional"))
    )
    (net (code "88") (name "USB2-ISNS") (class "Default")
      (node (ref "C4") (pin "1") (pinfunction "1_1") (pintype "passive"))
      (node (ref "R16") (pin "2") (pinfunction "2_2") (pintype "passive"))
      (node (ref "U5") (pin "B1") (pinfunction "B1_B1") (pintype "bidirectional"))
    )
    (net (code "89") (name "USB2-TSNS") (class "Default")
      (node (ref "C3") (pin "1") (pinfunction "1_1") (pintype "passive"))
      (node (ref "J1") (pin "2") (pinfunction "2_2") (pintype "passive"))
      (node (ref "R9") (pin "1") (pinfunction "1_1") (pintype "passive"))
      (node (ref "U5") (pin "A3") (pinfunction "A3_A3") (pintype "bidirectional"))
    )
    (net (code "90") (name "USB2-VCC-SW") (class "Default")
      (node (ref "CON1") (pin "1-5V") (pinfunction "VCC_1-5V") (pintype "bidirectional"))
      (node (ref "Q3") (pin "5") (pinfunction "D_5") (pintype "bidirectional"))
      (node (ref "Q3") (pin "6") (pinfunction "D_6") (pintype "bidirectional"))
      (node (ref "Q3") (pin "7") (pinfunction "D_7") (pintype "bidirectional"))
      (node (ref "Q3") (pin "8") (pinfunction "D_8") (pintype "bidirectional"))
      (node (ref "R3") (pin "2") (pinfunction "2_2") (pintype "passive"))
    )
    (net (code "91") (name "USB2-VSNS") (class "Default")
      (node (ref "C2") (pin "1") (pinfunction "1_1") (pintype "passive"))
      (node (ref "R3") (pin "1") (pinfunction "1_1") (pintype "passive"))
      (node (ref "R4") (pin "2") (pinfunction "2_2") (pintype "passive"))
      (node (ref "U5") (pin "B0") (pinfunction "B0_B0") (pintype "bidirectional"))
    )
    (net (code "92") (name "USB2VIN") (class "Default")
      (node (ref "CON2") (pin "1-VCC") (pinfunction "VCC_1-VCC") (pintype "bidirectional"))
      (node (ref "D2") (pin "A") (pinfunction "ANODE_A") (pintype "passive"))
      (node (ref "D9") (pin "A") (pinfunction "ANODE_A") (pintype "passive"))
      (node (ref "R11") (pin "2") (pinfunction "2_2") (pintype "passive"))
      (node (ref "R7") (pin "2") (pinfunction "2_2") (pintype "passive"))
      (node (ref "R8") (pin "2") (pinfunction "2_2") (pintype "passive"))
    )
    (net (code "93") (name "USB3-EN") (class "Default")
      (node (ref "Q10") (pin "1") (pinfunction "G_1") (pintype "bidirectional"))
      (node (ref "R20") (pin "1") (pinfunction "1_1") (pintype "passive"))
      (node (ref "U5") (pin "B10") (pinfunction "B10_B10") (pintype "bidirectional"))
    )
    (net (code "94") (name "USB3-ISNS") (class "Default")
      (node (ref "C14") (pin "1") (pinfunction "1_1") (pintype "passive"))
      (node (ref "R37") (pin "2") (pinfunction "2_2") (pintype "passive"))
      (node (ref "U5") (pin "A7") (pinfunction "A7_A7") (pintype "bidirectional"))
    )
    (net (code "95") (name "USB3-TSNS") (class "Default")
      (node (ref "C11") (pin "1") (pinfunction "1_1") (pintype "passive"))
      (node (ref "J2") (pin "2") (pinfunction "2_2") (pintype "passive"))
      (node (ref "R30") (pin "1") (pinfunction "1_1") (pintype "passive"))
      (node (ref "U5") (pin "A2") (pinfunction "A2_A2") (pintype "bidirectional"))
    )
    (net (code "96") (name "USB3-VCC-SW") (class "Default")
      (node (ref "CON3") (pin "1-VBUS") (pinfunction "VBUS_1-VBUS") (pintype "bidirectional"))
      (node (ref "Q9") (pin "5") (pinfunction "D_5") (pintype "bidirectional"))
      (node (ref "Q9") (pin "6") (pinfunction "D_6") (pintype "bidirectional"))
      (node (ref "Q9") (pin "7") (pinfunction "D_7") (pintype "bidirectional"))
      (node (ref "Q9") (pin "8") (pinfunction "D_8") (pintype "bidirectional"))
      (node (ref "R21") (pin "2") (pinfunction "2_2") (pintype "passive"))
    )
    (net (code "97") (name "USB3-VSNS") (class "Default")
      (node (ref "C6") (pin "1") (pinfunction "1_1") (pintype "passive"))
      (node (ref "R21") (pin "1") (pinfunction "1_1") (pintype "passive"))
      (node (ref "R22") (pin "2") (pinfunction "2_2") (pintype "passive"))
      (node (ref "U5") (pin "A6") (pinfunction "A6_A6") (pintype "bidirectional"))
    )
    (net (code "98") (name "USB3VIN") (class "Default")
      (node (ref "CON4") (pin "1-VBUS") (pinfunction "VBUS_1-VBUS") (pintype "bidirectional"))
      (node (ref "D3") (pin "A") (pinfunction "ANODE_A") (pintype "passive"))
      (node (ref "D8") (pin "A") (pinfunction "ANODE_A") (pintype "passive"))
      (node (ref "R26") (pin "2") (pinfunction "2_2") (pintype "passive"))
      (node (ref "R27") (pin "2") (pinfunction "2_2") (pintype "passive"))
      (node (ref "R29") (pin "2") (pinfunction "2_2") (pintype "passive"))
    )
    (net (code "99") (name "USBBPIN") (class "Default")
      (node (ref "C16") (pin "1") (pinfunction "1_1") (pintype "passive"))
      (node (ref "C5") (pin "1") (pinfunction "1_1") (pintype "passive"))
      (node (ref "D4") (pin "A") (pinfunction "ANODE_A") (pintype "passive"))
      (node (ref "D7") (pin "A") (pinfunction "ANODE_A") (pintype "passive"))
      (node (ref "JP18") (pin "1") (pinfunction "1_1") (pintype "passive"))
      (node (ref "JP21") (pin "1") (pinfunction "1_1") (pintype "passive"))
      (node (ref "JP24") (pin "1") (pinfunction "1_1") (pintype "passive"))
      (node (ref "JP28") (pin "3") (pinfunction "3_3") (pintype "passive"))
      (node (ref "JP30") (pin "1") (pinfunction "1_1") (pintype "passive"))
      (node (ref "JP33") (pin "1") (pinfunction "1_1") (pintype "passive"))
      (node (ref "JP36") (pin "1") (pinfunction "1_1") (pintype "passive"))
      (node (ref "R18") (pin "1") (pinfunction "1_1") (pintype "passive"))
      (node (ref "U3") (pin "3") (pinfunction "VIN_3") (pintype "bidirectional"))
      (node (ref "U5") (pin "5V") (pinfunction "5V_5V") (pintype "bidirectional"))
    )
    (net (code "100") (name "VUSBMAX") (class "Default")
      (node (ref "C1") (pin "1") (pinfunction "1_1") (pintype "passive"))
      (node (ref "D2") (pin "K") (pinfunction "CATHODE_K") (pintype "passive"))
      (node (ref "D3") (pin "K") (pinfunction "CATHODE_K") (pintype "passive"))
      (node (ref "D4") (pin "K") (pinfunction "CATHODE_K") (pintype "passive"))
      (node (ref "U1") (pin "8") (pinfunction "VCC_8") (pintype "power_in"))
    )
    (net (code "101") (name "unconnected-(CON2-ID-Pad4-ID)") (class "Default")
      (node (ref "CON2") (pin "4-ID") (pinfunction "ID_4-ID") (pintype "bidirectional"))
    )
    (net (code "102") (name "unconnected-(U5-PadRST)") (class "Default")
      (node (ref "U5") (pin "RST") (pinfunction "RST_RST") (pintype "bidirectional"))
    )
    (net (code "103") (name "unconnected-(U5-VB-PadVBAT)") (class "Default")
      (node (ref "U5") (pin "VBAT") (pinfunction "VB_VBAT") (pintype "bidirectional"))
    )
  )
)
